# Sheet1.net
KiCad netlist of a schematic drawn in Altium Designer
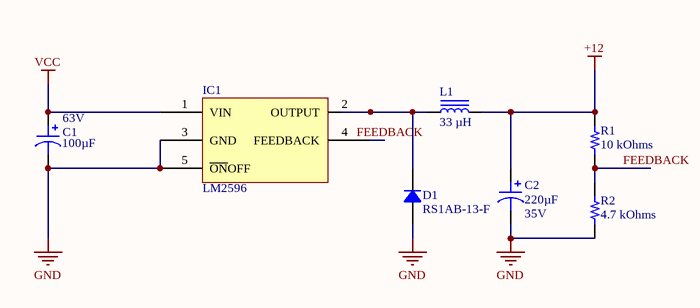
[diagram p0: Sheet1.SchDoc]

(export (version "E")
  (design (tool "Eeschema 10.0.6"))
  (components
    (comp (ref "C1")
      (value "100µF")
      (footprint "CAP TH ALUM ELEC D10.00mm S5.00mm H10.50mm")
      (description "CAP ALUM 100UF 20% 63V RADIAL")
      (fields
        (field (name "PART NUMBER") "URS1J101MPD1TD")
        (field (name "MANUFACTURER") "Nichicon")
        (field (name "VOLTAGE - RATED") "63V")
      )
      (libsource (lib "Celestial Altium Library - altium_library") (part "Polarised Capacitor"))
    )
    (comp (ref "C2")
      (value "220µF")
      (footprint "CAP ALSMD 8.3MM H10.5MM")
      (description "CAP ALUM 220UF 20% 35V SMD")
      (fields
        (field (name "PART NUMBER") "UUR1V221MNL6GS")
        (field (name "MANUFACTURER") "Nichicon")
        (field (name "VOLTAGE - RATED") "35V")
      )
      (libsource (lib "Celestial Altium Library - altium_library") (part "Polarised Capacitor"))
    )
    (comp (ref "D1")
      (value "RS1AB-13-F")
      (footprint "DO214AA SMB")
      (description "DIODE GEN PURP 50V 1A SMB")
      (fields (field (name "MANUFACTURER") "Diodes Incorporated"))
      (libsource (lib "Celestial Altium Library - altium_library") (part "Diode"))
    )
    (comp (ref "IC1") (value "LM2596") (footprint "D2PAC") (libsource (lib "Alitumlib") (part "LM2596")))
    (comp (ref "L1")
      (value "33 µH")
      (footprint "BOURNS SRR1280")
      (description "FIXED IND 33UH 3.5A 57 MOHM SMD")
      (fields (field (name "PART NUMBER") "SRR1280-330M") (field (name "MANUFACTURER") "Bourns Inc."))
      (libsource (lib "Celestial Altium Library - altium_library") (part "Inductor"))
    )
    (comp (ref "R1")
      (value "10 kOhms")
      (footprint "RES 0805_2012")
      (description "RES SMD 4.7K OHM 5% 1/2W 0805")
      (fields (field (name "PART NUMBER") "CRCW08054K70JNEAHP") (field (name "MANUFACTURER") "Vishay Dale"))
      (libsource (lib "Celestial Altium Library - altium_library") (part "Resistor"))
    )
    (comp (ref "R2")
      (value "4.7 kOhms")
      (footprint "RES 0805_2012")
      (description "RES SMD 4.7K OHM 5% 1/2W 0805")
      (fields (field (name "PART NUMBER") "CRCW08054K70JNEAHP") (field (name "MANUFACTURER") "Vishay Dale"))
      (libsource (lib "Celestial Altium Library - altium_library") (part "Resistor"))
    )
  )
  (nets
    (net (code "1") (name "+12") (class "Default")
      (node (ref "C2") (pin "1") (pinfunction "1_1") (pintype "passive"))
      (node (ref "L1") (pin "2") (pinfunction "2_2") (pintype "passive"))
      (node (ref "R1") (pin "1") (pinfunction "1_1") (pintype "passive"))
    )
    (net (code "2") (name "/FEEDBACK") (class "Default")
      (node (ref "R1") (pin "2") (pinfunction "2_2") (pintype "passive"))
      (node (ref "R2") (pin "2") (pinfunction "2_2") (pintype "passive"))
    )
    (net (code "3") (name "GND") (class "Default")
      (node (ref "C1") (pin "2") (pinfunction "2_2") (pintype "passive"))
      (node (ref "C2") (pin "2") (pinfunction "2_2") (pintype "passive"))
      (node (ref "D1") (pin "1") (pinfunction "1_1") (pintype "passive"))
      (node (ref "IC1") (pin "3") (pinfunction "GND_3") (pintype "passive"))
      (node (ref "IC1") (pin "5") (pinfunction "~{ON}OFF_5") (pintype "passive"))
      (node (ref "R2") (pin "1") (pinfunction "1_1") (pintype "passive"))
    )
    (net (code "4") (name "Net-(IC1-OUTPUT)") (class "Default")
      (node (ref "D1") (pin "2") (pinfunction "2_2") (pintype "passive"))
      (node (ref "IC1") (pin "2") (pinfunction "OUTPUT_2") (pintype "passive"))
      (node (ref "L1") (pin "1") (pinfunction "1_1") (pintype "passive"))
    )
    (net (code "5") (name "VCC") (class "Default")
      (node (ref "C1") (pin "1") (pinfunction "1_1") (pintype "passive"))
      (node (ref "IC1") (pin "1") (pinfunction "VIN_1") (pintype "passive"))
    )
    (net (code "6") (name "unconnected-(IC1-FEEDBACK-Pad4)") (class "Default")
      (node (ref "IC1") (pin "4") (pinfunction "FEEDBACK_4") (pintype "passive"))
    )
  )
)
